# Power_Dist_Motor.net
KiCad netlist of a schematic drawn in EAGLE
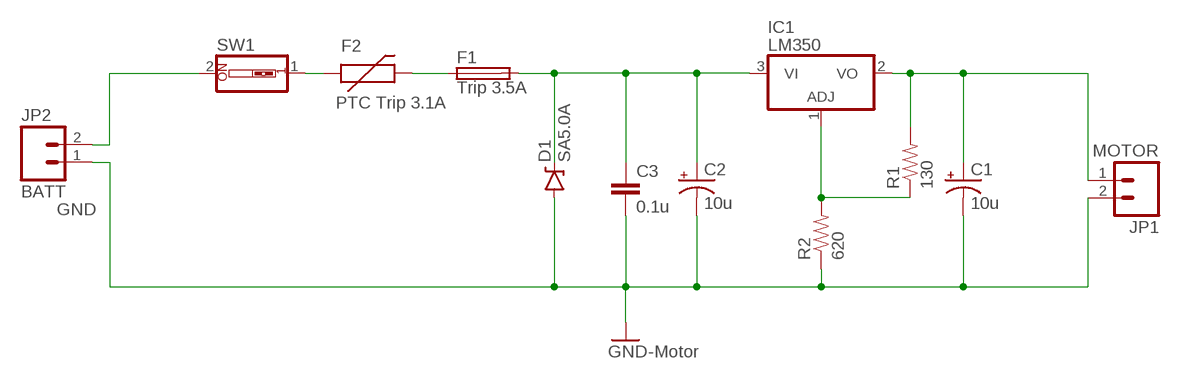
[diagram p0: schematic, sheet 1]

(export (version "E")
  (design (tool "Eeschema 10.0.6"))
  (components
    (comp (ref "C1")
      (value "10u")
      (footprint "eagle-import:CPOL-RADIAL-10UF-25V")
      (libsource (lib "eagle-import") (part "CAP_POLPTH2"))
    )
    (comp (ref "C2")
      (value "10u")
      (footprint "eagle-import:CPOL-RADIAL-10UF-25V")
      (libsource (lib "eagle-import") (part "CAP_POLPTH2"))
    )
    (comp (ref "C3")
      (value "0.1u")
      (footprint "eagle-import:CAP-PTH-SMALL")
      (libsource (lib "eagle-import") (part "CAPPTH"))
    )
    (comp (ref "D1")
      (value "SA5.0A")
      (footprint "eagle-import:DIODE-BZT52")
      (libsource (lib "eagle-import") (part "DIODE-ZENER"))
    )
    (comp (ref "F1")
      (value "Trip 3.5A")
      (footprint "eagle-import:PICOFUSE")
      (libsource (lib "eagle-import") (part "PICOFUSE"))
    )
    (comp (ref "F2")
      (value "PTC Trip 3.1A")
      (footprint "eagle-import:PTC")
      (libsource (lib "eagle-import") (part "PTCPTH"))
    )
    (comp (ref "IC1")
      (value "LM350")
      (footprint "eagle-import:TO220H")
      (libsource (lib "eagle-import") (part "317T"))
    )
    (comp (ref "JP1")
      (value "MOTOR")
      (footprint "eagle-import:1X02")
      (libsource (lib "eagle-import") (part "M02PTH"))
    )
    (comp (ref "JP2")
      (value "BATT")
      (footprint "eagle-import:1X02")
      (libsource (lib "eagle-import") (part "M02PTH"))
    )
    (comp (ref "R1")
      (value "130")
      (footprint "eagle-import:AXIAL-0.4")
      (libsource (lib "eagle-import") (part "RESISTORPTH-1/4W"))
    )
    (comp (ref "R2")
      (value "620")
      (footprint "eagle-import:AXIAL-0.4")
      (libsource (lib "eagle-import") (part "RESISTORPTH-1/4W"))
    )
    (comp (ref "SW1")
      (value "SW_DIP-1")
      (footprint "eagle-import:EDG-01")
      (libsource (lib "eagle-import") (part "SW_DIP-1"))
    )
  )
  (nets
    (net (code "1") (name "GND-Motor") (class "Default")
      (node (ref "C1") (pin "2") (pinfunction "-_2") (pintype "passive"))
      (node (ref "C2") (pin "2") (pinfunction "-_2") (pintype "passive"))
      (node (ref "C3") (pin "2") (pinfunction "2_2") (pintype "passive"))
      (node (ref "D1") (pin "A") (pinfunction "A_A") (pintype "passive"))
      (node (ref "JP1") (pin "2") (pinfunction "2_2") (pintype "passive"))
      (node (ref "JP2") (pin "1") (pinfunction "1_1") (pintype "passive"))
      (node (ref "R2") (pin "P$1") (pinfunction "1_P$1") (pintype "passive"))
    )
    (net (code "2") (name "Net-(C1-+)") (class "Default")
      (node (ref "C1") (pin "1") (pinfunction "+_1") (pintype "passive"))
      (node (ref "IC1") (pin "2") (pinfunction "VO_2") (pintype "passive"))
      (node (ref "JP1") (pin "1") (pinfunction "1_1") (pintype "passive"))
      (node (ref "R1") (pin "P$2") (pinfunction "2_P$2") (pintype "passive"))
    )
    (net (code "3") (name "Net-(C2-+)") (class "Default")
      (node (ref "C2") (pin "1") (pinfunction "+_1") (pintype "passive"))
      (node (ref "C3") (pin "1") (pinfunction "1_1") (pintype "passive"))
      (node (ref "D1") (pin "C") (pinfunction "C_C") (pintype "passive"))
      (node (ref "F1") (pin "2") (pinfunction "2_2") (pintype "passive"))
      (node (ref "IC1") (pin "3") (pinfunction "VI_3") (pintype "input"))
    )
    (net (code "4") (name "Net-(F2-1)") (class "Default")
      (node (ref "F2") (pin "P$1") (pinfunction "1_P$1") (pintype "bidirectional"))
      (node (ref "SW1") (pin "1") (pinfunction "1_1") (pintype "passive"))
    )
    (net (code "5") (name "Net-(F2-2)") (class "Default")
      (node (ref "F1") (pin "1") (pinfunction "1_1") (pintype "passive"))
      (node (ref "F2") (pin "P$2") (pinfunction "2_P$2") (pintype "bidirectional"))
    )
    (net (code "6") (name "Net-(IC1-ADJ)") (class "Default")
      (node (ref "IC1") (pin "1") (pinfunction "ADJ_1") (pintype "input"))
      (node (ref "R1") (pin "P$1") (pinfunction "1_P$1") (pintype "passive"))
      (node (ref "R2") (pin "P$2") (pinfunction "2_P$2") (pintype "passive"))
    )
    (net (code "7") (name "Net-(JP2-Pad2)") (class "Default")
      (node (ref "JP2") (pin "2") (pinfunction "2_2") (pintype "passive"))
      (node (ref "SW1") (pin "2") (pinfunction "2_2") (pintype "passive"))
    )
  )
)
